# WL-AUDIO.net
KiCad netlist of a schematic drawn in Altium Designer
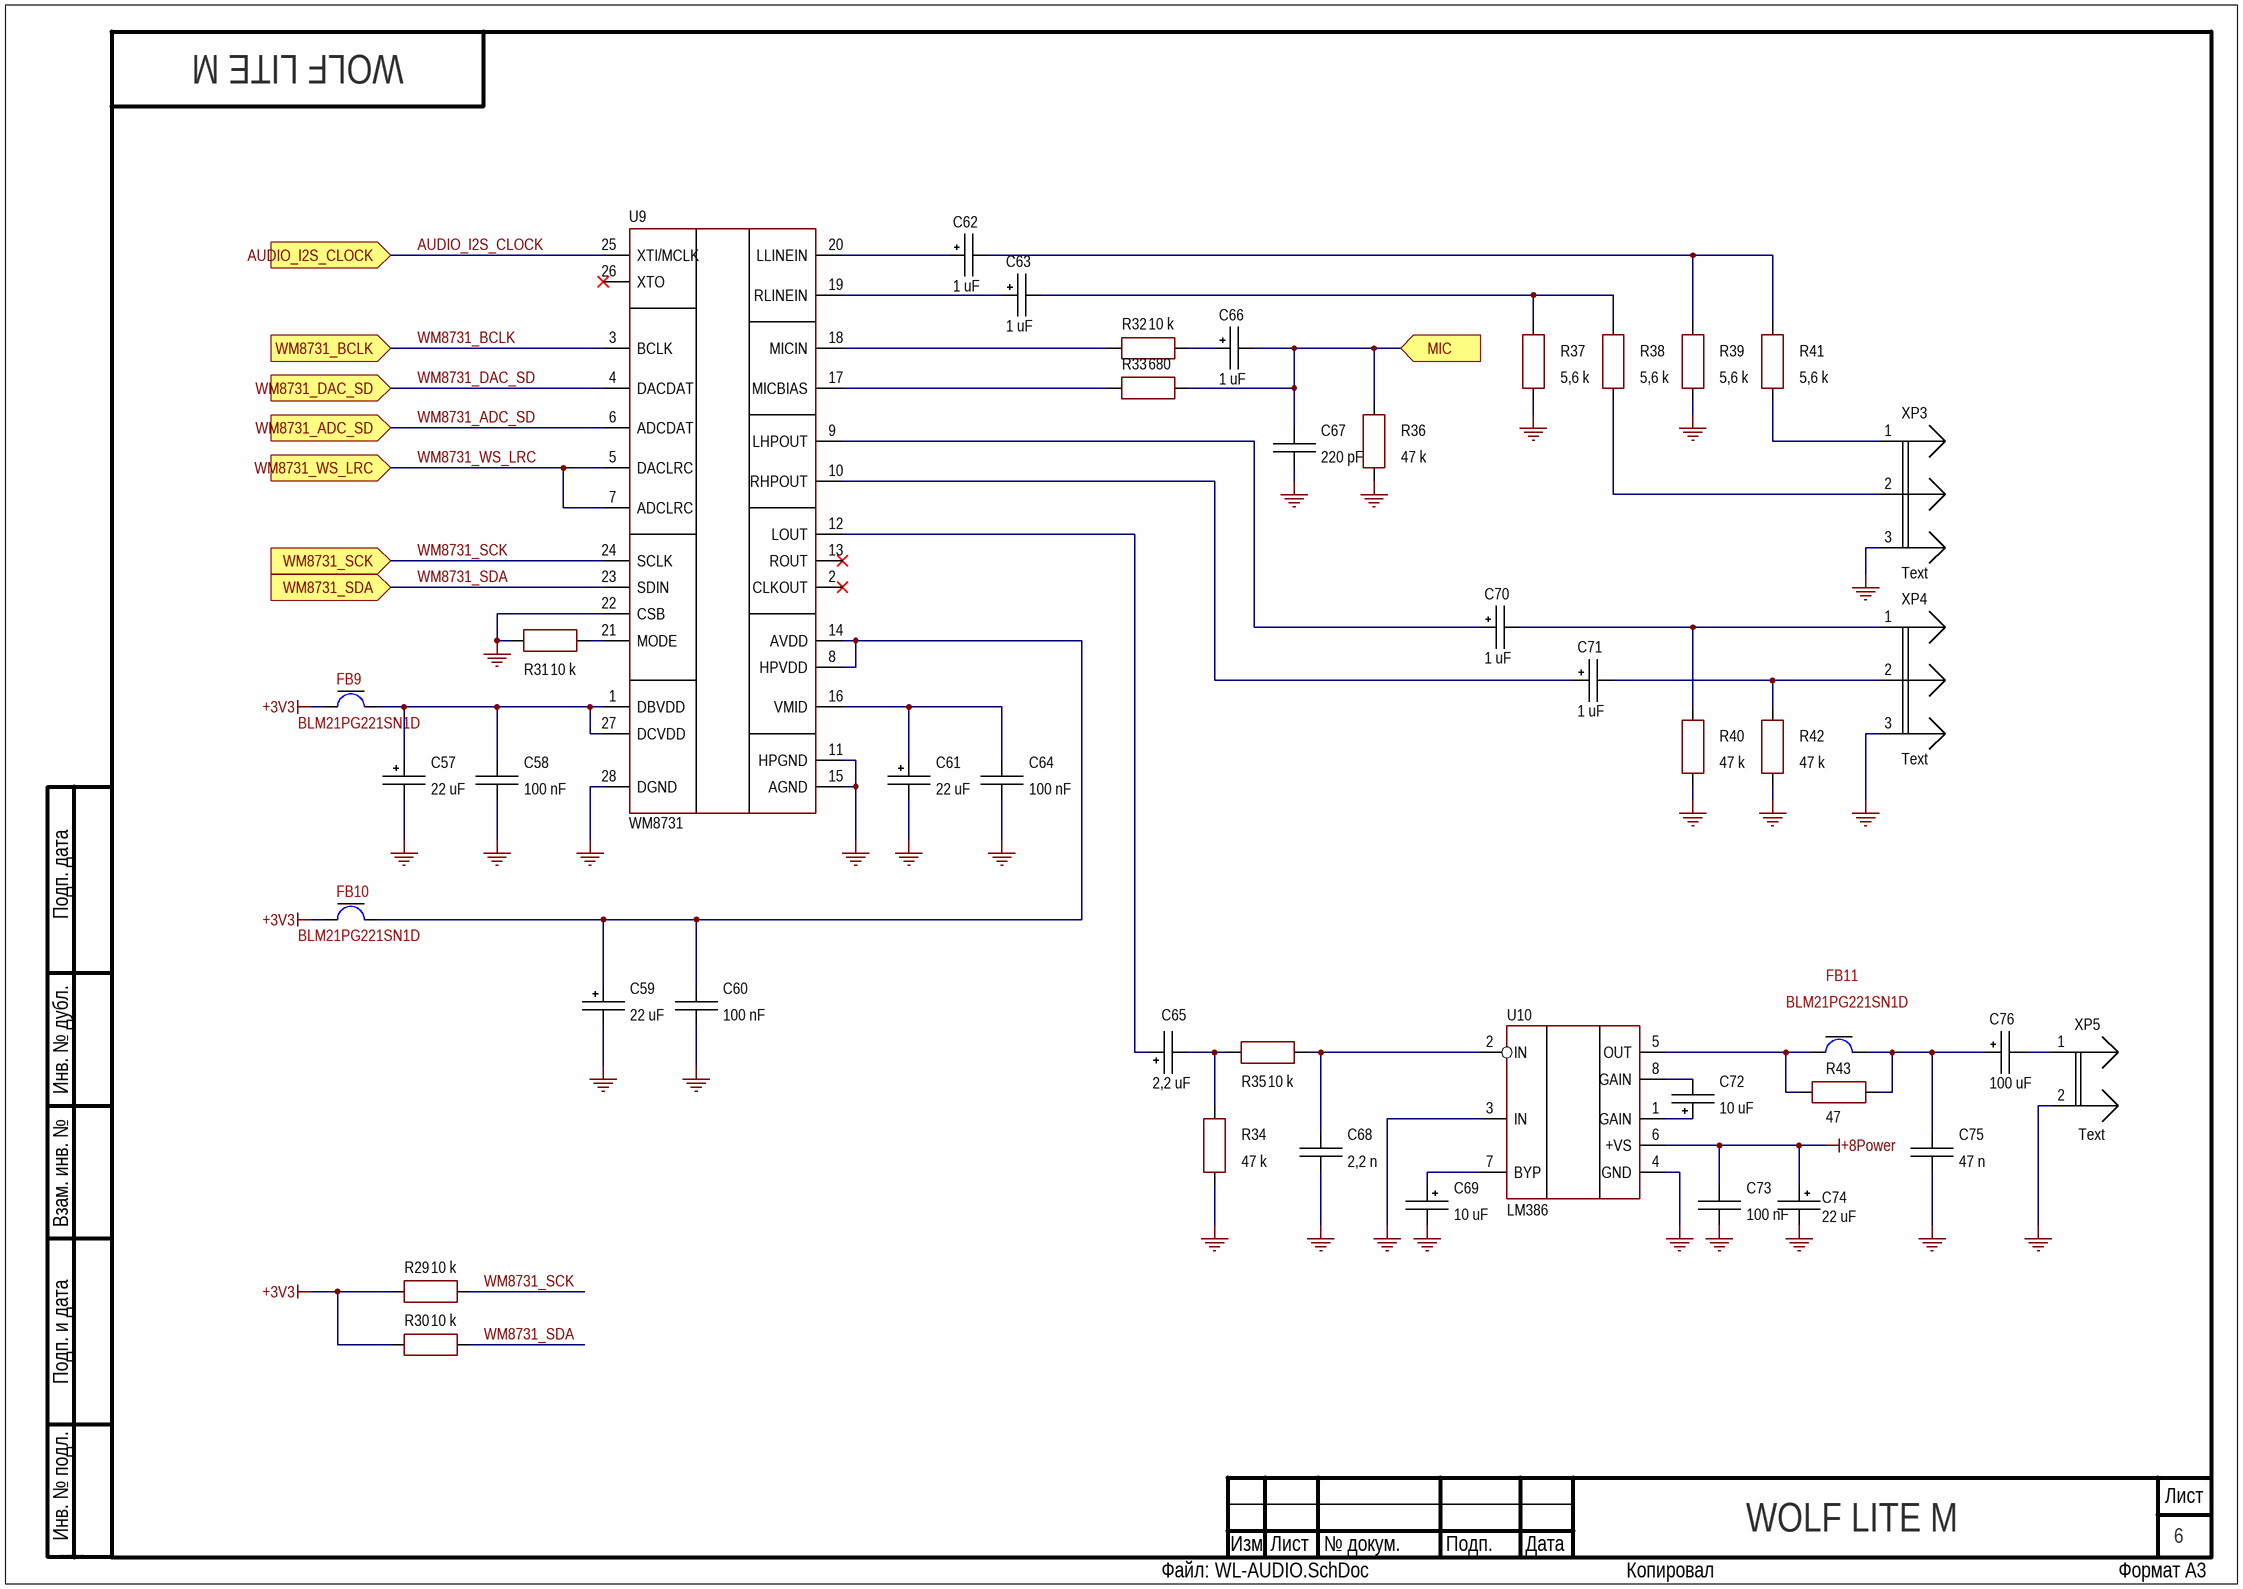
[diagram p0: WL-AUDIO.SchDoc]

(export (version "E")
  (design (tool "Eeschema 10.0.6"))
  (components
    (comp (ref "C57")
      (value "22 uF")
      (footprint "CAP-CASE B")
      (fields
        (field (name "MANUFACTURER") "Panasonic Electronic Components")
        (field (name "PART NUMBER") "EEE-1CA220WAR")
        (field (name "TOLERANCE") "±20%")
      )
      (libsource (lib "GOST") (part "Capacitor Polar"))
    )
    (comp (ref "C58")
      (value "100 nF")
      (footprint "C-0805-0.95")
      (fields
        (field (name "MANUFACTURER") "Yageo")
        (field (name "PART NUMBER") "CC0805KRX7R9BB104")
        (field (name "TOLERANCE") "±10%")
      )
      (libsource (lib "GOST") (part "Capacitor"))
    )
    (comp (ref "C59")
      (value "22 uF")
      (footprint "CAP-CASE B")
      (fields
        (field (name "MANUFACTURER") "Panasonic Electronic Components")
        (field (name "PART NUMBER") "EEE-1CA220WAR")
        (field (name "TOLERANCE") "±20%")
      )
      (libsource (lib "GOST") (part "Capacitor Polar"))
    )
    (comp (ref "C60")
      (value "100 nF")
      (footprint "C-0805-0.95")
      (fields
        (field (name "MANUFACTURER") "Yageo")
        (field (name "PART NUMBER") "CC0805KRX7R9BB104")
        (field (name "TOLERANCE") "±10%")
      )
      (libsource (lib "GOST") (part "Capacitor"))
    )
    (comp (ref "C61")
      (value "22 uF")
      (footprint "CAP-CASE B")
      (fields
        (field (name "MANUFACTURER") "Panasonic Electronic Components")
        (field (name "PART NUMBER") "EEE-1CA220WAR")
        (field (name "TOLERANCE") "±20%")
      )
      (libsource (lib "GOST") (part "Capacitor Polar"))
    )
    (comp (ref "C62")
      (value "1 uF")
      (footprint "CAP-CASE B")
      (fields
        (field (name "MANUFACTURER") "Panasonic Electronic Components")
        (field (name "PART NUMBER") "EEE-1HA010SR")
        (field (name "TOLERANCE") "±20%")
      )
      (libsource (lib "GOST") (part "Capacitor Polar"))
    )
    (comp (ref "C63")
      (value "1 uF")
      (footprint "CAP-CASE B")
      (fields
        (field (name "MANUFACTURER") "Panasonic Electronic Components")
        (field (name "PART NUMBER") "EEE-1HA010SR")
        (field (name "TOLERANCE") "±20%")
      )
      (libsource (lib "GOST") (part "Capacitor Polar"))
    )
    (comp (ref "C64")
      (value "100 nF")
      (footprint "C-0805-0.95")
      (fields
        (field (name "MANUFACTURER") "Yageo")
        (field (name "PART NUMBER") "CC0805KRX7R9BB104")
        (field (name "TOLERANCE") "±10%")
      )
      (libsource (lib "GOST") (part "Capacitor"))
    )
    (comp (ref "C65")
      (value "2,2 uF")
      (footprint "CAP-CASE B")
      (fields
        (field (name "PART NUMBER") "EEE-1HA2R2AR")
        (field (name "MANUFACTURER") "Panasonic Electronic Components")
        (field (name "TOLERANCE") "±20%")
      )
      (libsource (lib "GOST") (part "Capacitor Polar"))
    )
    (comp (ref "C66")
      (value "1 uF")
      (footprint "CAP-CASE B")
      (fields
        (field (name "MANUFACTURER") "Panasonic Electronic Components")
        (field (name "PART NUMBER") "EEE-1HA010SR")
        (field (name "TOLERANCE") "±20%")
      )
      (libsource (lib "GOST") (part "Capacitor Polar"))
    )
    (comp (ref "C67")
      (value "220 pF")
      (footprint "C-0805-0.7")
      (fields
        (field (name "MANUFACTURER") "Yageo")
        (field (name "PART NUMBER") "CC0805JRNPO9BN221")
        (field (name "TOLERANCE") "±5%")
      )
      (libsource (lib "GOST") (part "Capacitor"))
    )
    (comp (ref "C68")
      (value "2,2 n")
      (footprint "C-0805-0.7")
      (fields
        (field (name "PART NUMBER") "CC0805KRX7R9BB222")
        (field (name "TOLERANCE") "±10%")
        (field (name "VOLTAGE") "50 V")
      )
      (libsource (lib "GOST") (part "Capacitor"))
    )
    (comp (ref "C69")
      (value "10 uF")
      (footprint "CAP-CASE B")
      (fields
        (field (name "PART NUMBER") "EEE-1EA100WR")
        (field (name "TOLERANCE") "±20%")
        (field (name "VOLTAGE") "25 V")
      )
      (libsource (lib "GOST") (part "Capacitor Polar"))
    )
    (comp (ref "C70")
      (value "1 uF")
      (footprint "CAP-CASE B")
      (fields
        (field (name "MANUFACTURER") "Panasonic Electronic Components")
        (field (name "PART NUMBER") "EEE-1HA010SR")
        (field (name "TOLERANCE") "±20%")
      )
      (libsource (lib "GOST") (part "Capacitor Polar"))
    )
    (comp (ref "C71")
      (value "1 uF")
      (footprint "CAP-CASE B")
      (fields
        (field (name "MANUFACTURER") "Panasonic Electronic Components")
        (field (name "PART NUMBER") "EEE-1HA010SR")
        (field (name "TOLERANCE") "±20%")
      )
      (libsource (lib "GOST") (part "Capacitor Polar"))
    )
    (comp (ref "C72")
      (value "10 uF")
      (footprint "CAP-CASE B")
      (fields
        (field (name "PART NUMBER") "EEE-1EA100WR")
        (field (name "TOLERANCE") "±20%")
        (field (name "VOLTAGE") "25 V")
      )
      (libsource (lib "GOST") (part "Capacitor Polar"))
    )
    (comp (ref "C73")
      (value "100 nF")
      (footprint "C-0805-0.95")
      (fields
        (field (name "MANUFACTURER") "Yageo")
        (field (name "PART NUMBER") "CC0805KRX7R9BB104")
        (field (name "TOLERANCE") "±10%")
      )
      (libsource (lib "GOST") (part "Capacitor"))
    )
    (comp (ref "C74")
      (value "22 uF")
      (footprint "CAP-CASE B")
      (fields
        (field (name "PART NUMBER") "EEE-1CA220WAR")
        (field (name "TOLERANCE") "±20%")
        (field (name "VOLTAGE") "16 V")
      )
      (libsource (lib "GOST") (part "Capacitor Polar"))
    )
    (comp (ref "C75")
      (value "47 n")
      (footprint "C-0805-0.95")
      (fields
        (field (name "PART NUMBER") "CC0805KRX7R9BB473")
        (field (name "TOLERANCE") "±10%")
        (field (name "VOLTAGE") "50 V")
      )
      (libsource (lib "GOST") (part "Capacitor"))
    )
    (comp (ref "C76")
      (value "100 uF")
      (footprint "CAP-CASE E")
      (fields
        (field (name "PART NUMBER") "EEE-1CA101P")
        (field (name "TOLERANCE") "±20%")
        (field (name "VOLTAGE") "16 V")
      )
      (libsource (lib "GOST") (part "Capacitor Polar"))
    )
    (comp (ref "FB9")
      (value "BLM21PG221SN1D")
      (footprint "L-0805")
      (fields (field (name "MANUFACTURER") "Murata Electronics"))
      (libsource (lib "GOST") (part "Ferrite Bead"))
    )
    (comp (ref "FB10")
      (value "BLM21PG221SN1D")
      (footprint "L-0805")
      (fields (field (name "MANUFACTURER") "Murata Electronics"))
      (libsource (lib "GOST") (part "Ferrite Bead"))
    )
    (comp (ref "FB11")
      (value "BLM21PG221SN1D")
      (footprint "L-0805")
      (fields (field (name "MANUFACTURER") "Murata Electronics"))
      (libsource (lib "") (part "Ferrite Bead_1"))
    )
    (comp (ref "R29")
      (value "10 k")
      (footprint "R-0805")
      (fields
        (field (name "MANUFACTURER") "Yageo")
        (field (name "PART NUMBER") "RC0805JR-0710KL")
        (field (name "POWER") "0,125 W")
      )
      (libsource (lib "") (part "Resistor_1"))
    )
    (comp (ref "R30")
      (value "10 k")
      (footprint "R-0805")
      (fields
        (field (name "MANUFACTURER") "Yageo")
        (field (name "PART NUMBER") "RC0805JR-0710KL")
        (field (name "POWER") "0,125 W")
      )
      (libsource (lib "") (part "Resistor_1"))
    )
    (comp (ref "R31")
      (value "10 k")
      (footprint "R-0805")
      (fields
        (field (name "MANUFACTURER") "Yageo")
        (field (name "PART NUMBER") "RC0805JR-0710KL")
        (field (name "POWER") "0,125 W")
      )
      (libsource (lib "") (part "Resistor_2"))
    )
    (comp (ref "R32")
      (value "10 k")
      (footprint "R-0805")
      (fields
        (field (name "MANUFACTURER") "Yageo")
        (field (name "PART NUMBER") "RC0805JR-0710KL")
        (field (name "POWER") "0,125 W")
      )
      (libsource (lib "") (part "Resistor_1"))
    )
    (comp (ref "R33")
      (value "680")
      (footprint "R-0805")
      (fields
        (field (name "MANUFACTURER") "Yageo")
        (field (name "PART NUMBER") "RC0805JR-07680RL")
        (field (name "POWER") "0,125 W")
      )
      (libsource (lib "") (part "Resistor_1"))
    )
    (comp (ref "R34")
      (value "47 k")
      (footprint "R-0805")
      (fields
        (field (name "PART NUMBER") "RC0805JR-0747KL")
        (field (name "POWER") "0,125 W")
        (field (name "TOLERANCE") "±5%")
      )
      (libsource (lib "") (part "Resistor_3"))
    )
    (comp (ref "R35")
      (value "10 k")
      (footprint "R-0805")
      (fields
        (field (name "MANUFACTURER") "Yageo")
        (field (name "PART NUMBER") "RC0805JR-0710KL")
        (field (name "POWER") "0,125 W")
      )
      (libsource (lib "") (part "Resistor_2"))
    )
    (comp (ref "R36")
      (value "47 k")
      (footprint "R-0805")
      (fields
        (field (name "MANUFACTURER") "Yageo")
        (field (name "PART NUMBER") "RC0805JR-0747KL")
        (field (name "POWER") "0,125 W")
      )
      (libsource (lib "") (part "Resistor_3"))
    )
    (comp (ref "R37")
      (value "5,6 k")
      (footprint "R-0805")
      (fields
        (field (name "MANUFACTURER") "Yageo")
        (field (name "PART NUMBER") "RC0805JR-075K6L")
        (field (name "POWER") "0,125 W")
      )
      (libsource (lib "") (part "Resistor_3"))
    )
    (comp (ref "R38")
      (value "5,6 k")
      (footprint "R-0805")
      (fields
        (field (name "MANUFACTURER") "Yageo")
        (field (name "PART NUMBER") "RC0805JR-075K6L")
        (field (name "POWER") "0,125 W")
      )
      (libsource (lib "GOST") (part "Resistor"))
    )
    (comp (ref "R39")
      (value "5,6 k")
      (footprint "R-0805")
      (fields
        (field (name "MANUFACTURER") "Yageo")
        (field (name "PART NUMBER") "RC0805JR-075K6L")
        (field (name "POWER") "0,125 W")
      )
      (libsource (lib "") (part "Resistor_3"))
    )
    (comp (ref "R40")
      (value "47 k")
      (footprint "R-0805")
      (fields
        (field (name "MANUFACTURER") "Yageo")
        (field (name "PART NUMBER") "RC0805JR-0747KL")
        (field (name "POWER") "0,125 W")
      )
      (libsource (lib "") (part "Resistor_3"))
    )
    (comp (ref "R41")
      (value "5,6 k")
      (footprint "R-0805")
      (fields
        (field (name "MANUFACTURER") "Yageo")
        (field (name "PART NUMBER") "RC0805JR-075K6L")
        (field (name "POWER") "0,125 W")
      )
      (libsource (lib "GOST") (part "Resistor"))
    )
    (comp (ref "R42")
      (value "47 k")
      (footprint "R-0805")
      (fields
        (field (name "MANUFACTURER") "Yageo")
        (field (name "PART NUMBER") "RC0805JR-0747KL")
        (field (name "POWER") "0,125 W")
      )
      (libsource (lib "") (part "Resistor_3"))
    )
    (comp (ref "R43")
      (value "47")
      (footprint "R-0805")
      (fields
        (field (name "PART NUMBER") "RC0805JR-0747RL")
        (field (name "POWER") "0,125 W")
        (field (name "TOLERANCE") "±5%")
      )
      (libsource (lib "") (part "Resistor_1"))
    )
    (comp (ref "U9")
      (value "WM8731")
      (footprint "SSOP-28")
      (description "IC CODEC")
      (fields (field (name "PART NUMBER") "WM8731SEDS/RV") (field (name "MANUFACTURER") "Cirrus Logic Inc."))
      (libsource (lib "GOST") (part "WM8731SEDS/RV"))
    )
    (comp (ref "U10")
      (value "LM386")
      (footprint "SOIC-8")
      (description "IC AMP CLASS AB MONO")
      (fields (field (name "PART NUMBER") "LM386M-1/NOPB") (field (name "MANUFACTURER") "Texas Instruments"))
      (libsource (lib "GOST") (part "LM386"))
    )
    (comp (ref "XP3")
      (value "Text")
      (footprint "61900311121")
      (fields (field (name "PART NUMBER") "61900311121") (field (name "MANUFACTURER") "Würth Elektronik"))
      (libsource (lib "GOST") (part "Con-3-M"))
    )
    (comp (ref "XP4")
      (value "Text")
      (footprint "61900311121")
      (fields (field (name "PART NUMBER") "61900311121") (field (name "MANUFACTURER") "Würth Elektronik"))
      (libsource (lib "GOST") (part "Con-3-M"))
    )
    (comp (ref "XP5")
      (value "Text")
      (footprint "61900211121")
      (fields (field (name "PART NUMBER") "61900211121") (field (name "MANUFACTURER") "Würth Elektronik"))
      (libsource (lib "GOST") (part "Con-2-M"))
    )
  )
  (nets
    (net (code "1") (name "+3V3") (class "Default")
      (node (ref "FB10") (pin "2") (pinfunction "2_2") (pintype "passive"))
      (node (ref "FB9") (pin "2") (pinfunction "2_2") (pintype "passive"))
      (node (ref "R29") (pin "1") (pinfunction "1_1") (pintype "passive"))
      (node (ref "R30") (pin "1") (pinfunction "1_1") (pintype "passive"))
    )
    (net (code "2") (name "+8Power") (class "Default")
      (node (ref "C73") (pin "1") (pinfunction "1_1") (pintype "passive"))
      (node (ref "C74") (pin "1") (pinfunction "1_1") (pintype "passive"))
      (node (ref "U10") (pin "6") (pinfunction "+VS_6") (pintype "passive"))
    )
    (net (code "3") (name "/AUDIO_I2S_CLOCK") (class "Default")
      (node (ref "U9") (pin "25") (pinfunction "XTI/MCLK_25") (pintype "passive"))
    )
    (net (code "4") (name "/MIC") (class "Default")
      (node (ref "C66") (pin "2") (pinfunction "2_2") (pintype "passive"))
      (node (ref "C67") (pin "1") (pinfunction "1_1") (pintype "passive"))
      (node (ref "R33") (pin "2") (pinfunction "2_2") (pintype "passive"))
      (node (ref "R36") (pin "2") (pinfunction "2_2") (pintype "passive"))
    )
    (net (code "5") (name "/WM8731_ADC_SD") (class "Default")
      (node (ref "U9") (pin "6") (pinfunction "ADCDAT_6") (pintype "passive"))
    )
    (net (code "6") (name "/WM8731_BCLK") (class "Default")
      (node (ref "U9") (pin "3") (pinfunction "BCLK_3") (pintype "passive"))
    )
    (net (code "7") (name "/WM8731_DAC_SD") (class "Default")
      (node (ref "U9") (pin "4") (pinfunction "DACDAT_4") (pintype "passive"))
    )
    (net (code "8") (name "/WM8731_SCK") (class "Default")
      (node (ref "R29") (pin "2") (pinfunction "2_2") (pintype "passive"))
      (node (ref "U9") (pin "24") (pinfunction "SCLK_24") (pintype "passive"))
    )
    (net (code "9") (name "/WM8731_SDA") (class "Default")
      (node (ref "R30") (pin "2") (pinfunction "2_2") (pintype "passive"))
      (node (ref "U9") (pin "23") (pinfunction "SDIN_23") (pintype "passive"))
    )
    (net (code "10") (name "/WM8731_WS_LRC") (class "Default")
      (node (ref "U9") (pin "5") (pinfunction "DACLRC_5") (pintype "passive"))
      (node (ref "U9") (pin "7") (pinfunction "ADCLRC_7") (pintype "passive"))
    )
    (net (code "11") (name "GND") (class "Default")
      (node (ref "C57") (pin "2") (pinfunction "2_2") (pintype "passive"))
      (node (ref "C58") (pin "2") (pinfunction "2_2") (pintype "passive"))
      (node (ref "C59") (pin "2") (pinfunction "2_2") (pintype "passive"))
      (node (ref "C60") (pin "2") (pinfunction "2_2") (pintype "passive"))
      (node (ref "C61") (pin "2") (pinfunction "2_2") (pintype "passive"))
      (node (ref "C64") (pin "2") (pinfunction "2_2") (pintype "passive"))
      (node (ref "C67") (pin "2") (pinfunction "2_2") (pintype "passive"))
      (node (ref "C68") (pin "1") (pinfunction "1_1") (pintype "passive"))
      (node (ref "C69") (pin "2") (pinfunction "2_2") (pintype "passive"))
      (node (ref "C73") (pin "2") (pinfunction "2_2") (pintype "passive"))
      (node (ref "C74") (pin "2") (pinfunction "2_2") (pintype "passive"))
      (node (ref "C75") (pin "1") (pinfunction "1_1") (pintype "passive"))
      (node (ref "R31") (pin "2") (pinfunction "2_2") (pintype "passive"))
      (node (ref "R34") (pin "1") (pinfunction "1_1") (pintype "passive"))
      (node (ref "R36") (pin "1") (pinfunction "1_1") (pintype "passive"))
      (node (ref "R37") (pin "1") (pinfunction "1_1") (pintype "passive"))
      (node (ref "R39") (pin "1") (pinfunction "1_1") (pintype "passive"))
      (node (ref "R40") (pin "1") (pinfunction "1_1") (pintype "passive"))
      (node (ref "R42") (pin "1") (pinfunction "1_1") (pintype "passive"))
      (node (ref "U10") (pin "3") (pinfunction "IN_3") (pintype "passive"))
      (node (ref "U10") (pin "4") (pinfunction "GND_4") (pintype "passive"))
      (node (ref "U9") (pin "11") (pinfunction "HPGND_11") (pintype "passive"))
      (node (ref "U9") (pin "15") (pinfunction "AGND_15") (pintype "passive"))
      (node (ref "U9") (pin "22") (pinfunction "CSB_22") (pintype "passive"))
      (node (ref "U9") (pin "28") (pinfunction "DGND_28") (pintype "passive"))
      (node (ref "XP3") (pin "3") (pintype "passive"))
      (node (ref "XP4") (pin "3") (pintype "passive"))
      (node (ref "XP5") (pin "2") (pintype "passive"))
    )
    (net (code "12") (name "Net-(C62-Pad2)") (class "Default")
      (node (ref "C62") (pin "2") (pinfunction "2_2") (pintype "passive"))
      (node (ref "R39") (pin "2") (pinfunction "2_2") (pintype "passive"))
      (node (ref "R41") (pin "1") (pinfunction "1_1") (pintype "passive"))
    )
    (net (code "13") (name "Net-(C63-Pad2)") (class "Default")
      (node (ref "C63") (pin "2") (pinfunction "2_2") (pintype "passive"))
      (node (ref "R37") (pin "2") (pinfunction "2_2") (pintype "passive"))
      (node (ref "R38") (pin "1") (pinfunction "1_1") (pintype "passive"))
    )
    (net (code "14") (name "Net-(C65-Pad2)") (class "Default")
      (node (ref "C65") (pin "2") (pinfunction "2_2") (pintype "passive"))
      (node (ref "R34") (pin "2") (pinfunction "2_2") (pintype "passive"))
      (node (ref "R35") (pin "2") (pinfunction "2_2") (pintype "passive"))
    )
    (net (code "15") (name "Net-(C66-Pad1)") (class "Default")
      (node (ref "C66") (pin "1") (pinfunction "1_1") (pintype "passive"))
      (node (ref "R32") (pin "2") (pinfunction "2_2") (pintype "passive"))
    )
    (net (code "16") (name "Net-(C68-Pad2)") (class "Default")
      (node (ref "C68") (pin "2") (pinfunction "2_2") (pintype "passive"))
      (node (ref "R35") (pin "1") (pinfunction "1_1") (pintype "passive"))
      (node (ref "U10") (pin "2") (pinfunction "IN_2") (pintype "passive"))
    )
    (net (code "17") (name "Net-(C70-Pad2)") (class "Default")
      (node (ref "C70") (pin "2") (pinfunction "2_2") (pintype "passive"))
      (node (ref "R40") (pin "2") (pinfunction "2_2") (pintype "passive"))
      (node (ref "XP4") (pin "1") (pintype "passive"))
    )
    (net (code "18") (name "Net-(C71-Pad2)") (class "Default")
      (node (ref "C71") (pin "2") (pinfunction "2_2") (pintype "passive"))
      (node (ref "R42") (pin "2") (pinfunction "2_2") (pintype "passive"))
      (node (ref "XP4") (pin "2") (pintype "passive"))
    )
    (net (code "19") (name "Net-(C72-Pad1)") (class "Default")
      (node (ref "C72") (pin "1") (pinfunction "1_1") (pintype "passive"))
      (node (ref "U10") (pin "1") (pinfunction "GAIN_1") (pintype "passive"))
    )
    (net (code "20") (name "Net-(C72-Pad2)") (class "Default")
      (node (ref "C72") (pin "2") (pinfunction "2_2") (pintype "passive"))
      (node (ref "U10") (pin "8") (pinfunction "GAIN_8") (pintype "passive"))
    )
    (net (code "21") (name "Net-(C75-Pad2)") (class "Default")
      (node (ref "C75") (pin "2") (pinfunction "2_2") (pintype "passive"))
      (node (ref "C76") (pin "1") (pinfunction "1_1") (pintype "passive"))
      (node (ref "FB11") (pin "2") (pinfunction "2_2") (pintype "passive"))
      (node (ref "R43") (pin "2") (pinfunction "2_2") (pintype "passive"))
    )
    (net (code "22") (name "Net-(C76-Pad2)") (class "Default")
      (node (ref "C76") (pin "2") (pinfunction "2_2") (pintype "passive"))
      (node (ref "XP5") (pin "1") (pintype "passive"))
    )
    (net (code "23") (name "Net-(R38-Pad2)") (class "Default")
      (node (ref "R38") (pin "2") (pinfunction "2_2") (pintype "passive"))
      (node (ref "XP3") (pin "2") (pintype "passive"))
    )
    (net (code "24") (name "Net-(R41-Pad2)") (class "Default")
      (node (ref "R41") (pin "2") (pinfunction "2_2") (pintype "passive"))
      (node (ref "XP3") (pin "1") (pintype "passive"))
    )
    (net (code "25") (name "Net-(U9-AVDD)") (class "Default")
      (node (ref "C59") (pin "1") (pinfunction "1_1") (pintype "passive"))
      (node (ref "C60") (pin "1") (pinfunction "1_1") (pintype "passive"))
      (node (ref "FB10") (pin "1") (pinfunction "1_1") (pintype "passive"))
      (node (ref "U9") (pin "14") (pinfunction "AVDD_14") (pintype "passive"))
      (node (ref "U9") (pin "8") (pinfunction "HPVDD_8") (pintype "passive"))
    )
    (net (code "26") (name "Net-(U9-DBVDD)") (class "Default")
      (node (ref "C57") (pin "1") (pinfunction "1_1") (pintype "passive"))
      (node (ref "C58") (pin "1") (pinfunction "1_1") (pintype "passive"))
      (node (ref "FB9") (pin "1") (pinfunction "1_1") (pintype "passive"))
      (node (ref "U9") (pin "1") (pinfunction "DBVDD_1") (pintype "passive"))
      (node (ref "U9") (pin "27") (pinfunction "DCVDD_27") (pintype "passive"))
    )
    (net (code "27") (name "Net-(U9-LHPOUT)") (class "Default")
      (node (ref "C70") (pin "1") (pinfunction "1_1") (pintype "passive"))
      (node (ref "U9") (pin "9") (pinfunction "LHPOUT_9") (pintype "passive"))
    )
    (net (code "28") (name "Net-(U9-LLINEIN)") (class "Default")
      (node (ref "C62") (pin "1") (pinfunction "1_1") (pintype "passive"))
      (node (ref "U9") (pin "20") (pinfunction "LLINEIN_20") (pintype "passive"))
    )
    (net (code "29") (name "Net-(U9-LOUT)") (class "Default")
      (node (ref "C65") (pin "1") (pinfunction "1_1") (pintype "passive"))
      (node (ref "U9") (pin "12") (pinfunction "LOUT_12") (pintype "passive"))
    )
    (net (code "30") (name "Net-(U9-MICBIAS)") (class "Default")
      (node (ref "R33") (pin "1") (pinfunction "1_1") (pintype "passive"))
      (node (ref "U9") (pin "17") (pinfunction "MICBIAS_17") (pintype "passive"))
    )
    (net (code "31") (name "Net-(U9-MICIN)") (class "Default")
      (node (ref "R32") (pin "1") (pinfunction "1_1") (pintype "passive"))
      (node (ref "U9") (pin "18") (pinfunction "MICIN_18") (pintype "passive"))
    )
    (net (code "32") (name "Net-(U9-MODE)") (class "Default")
      (node (ref "R31") (pin "1") (pinfunction "1_1") (pintype "passive"))
      (node (ref "U9") (pin "21") (pinfunction "MODE_21") (pintype "passive"))
    )
    (net (code "33") (name "Net-(U9-RHPOUT)") (class "Default")
      (node (ref "C71") (pin "1") (pinfunction "1_1") (pintype "passive"))
      (node (ref "U9") (pin "10") (pinfunction "RHPOUT_10") (pintype "passive"))
    )
    (net (code "34") (name "Net-(U9-RLINEIN)") (class "Default")
      (node (ref "C63") (pin "1") (pinfunction "1_1") (pintype "passive"))
      (node (ref "U9") (pin "19") (pinfunction "RLINEIN_19") (pintype "passive"))
    )
    (net (code "35") (name "Net-(U9-VMID)") (class "Default")
      (node (ref "C61") (pin "1") (pinfunction "1_1") (pintype "passive"))
      (node (ref "C64") (pin "1") (pinfunction "1_1") (pintype "passive"))
      (node (ref "U9") (pin "16") (pinfunction "VMID_16") (pintype "passive"))
    )
    (net (code "36") (name "Net-(U10-BYP)") (class "Default")
      (node (ref "C69") (pin "1") (pinfunction "1_1") (pintype "passive"))
      (node (ref "U10") (pin "7") (pinfunction "BYP_7") (pintype "passive"))
    )
    (net (code "37") (name "Net-(U10-OUT)") (class "Default")
      (node (ref "FB11") (pin "1") (pinfunction "1_1") (pintype "passive"))
      (node (ref "R43") (pin "1") (pinfunction "1_1") (pintype "passive"))
      (node (ref "U10") (pin "5") (pinfunction "OUT_5") (pintype "passive"))
    )
    (net (code "38") (name "unconnected-(U9-CLKOUT-Pad2)") (class "Default")
      (node (ref "U9") (pin "2") (pinfunction "CLKOUT_2") (pintype "passive+no_connect"))
    )
    (net (code "39") (name "unconnected-(U9-ROUT-Pad13)") (class "Default")
      (node (ref "U9") (pin "13") (pinfunction "ROUT_13") (pintype "passive+no_connect"))
    )
    (net (code "40") (name "unconnected-(U9-XTO-Pad26)") (class "Default")
      (node (ref "U9") (pin "26") (pinfunction "XTO_26") (pintype "passive+no_connect"))
    )
  )
)
